# ASD2112.net
KiCad netlist of a schematic drawn in EAGLE
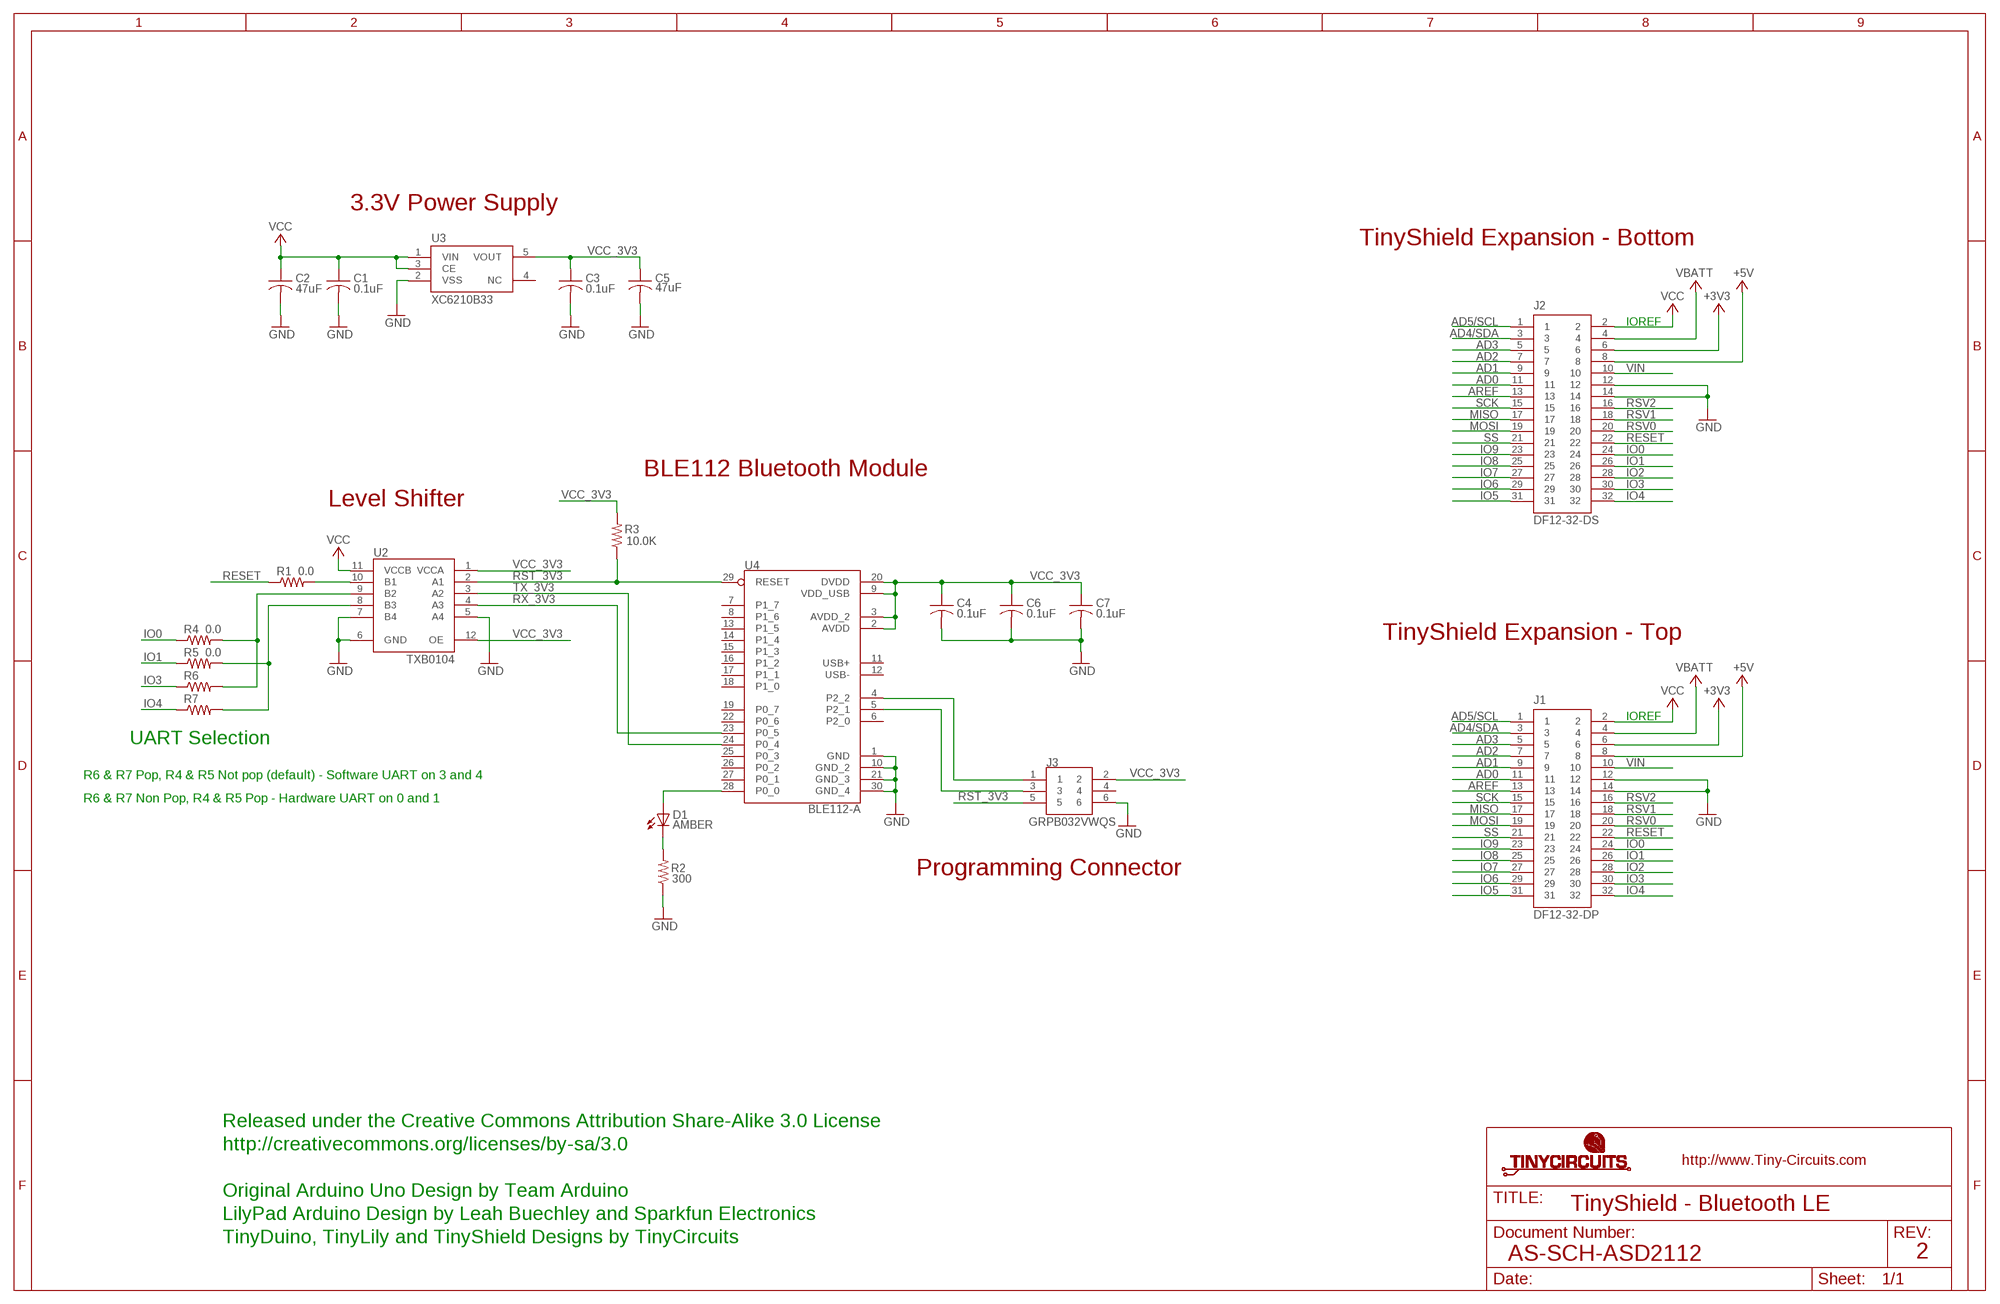
[diagram p0: schematic, sheet 1]

(export (version "E")
  (design (tool "Eeschema 10.0.6"))
  (components
    (comp (ref "C1")
      (value "0.1uF")
      (footprint "eagle-import:C0402")
      (fields (field (name "PARTNO") "AS-ITM-00008") (field (name "PARTNO_1") "AS-ITM-00008"))
      (libsource (lib "eagle-import") (part "AS-ITM-00008"))
    )
    (comp (ref "C2")
      (value "47uF")
      (footprint "eagle-import:C1206")
      (fields (field (name "PARTNUM") "AS-ITM-00049") (field (name "PARTNUM_1") "AS-ITM-00049"))
      (libsource (lib "eagle-import") (part "AS-ITM-00049"))
    )
    (comp (ref "C3")
      (value "0.1uF")
      (footprint "eagle-import:C0402")
      (fields (field (name "PARTNO") "AS-ITM-00008") (field (name "PARTNO_1") "AS-ITM-00008"))
      (libsource (lib "eagle-import") (part "AS-ITM-00008"))
    )
    (comp (ref "C4")
      (value "0.1uF")
      (footprint "eagle-import:C0402")
      (fields (field (name "PARTNO") "AS-ITM-00008") (field (name "PARTNO_1") "AS-ITM-00008"))
      (libsource (lib "eagle-import") (part "AS-ITM-00008"))
    )
    (comp (ref "C5")
      (value "47uF")
      (footprint "eagle-import:C1206")
      (fields (field (name "PARTNUM") "AS-ITM-00049"))
      (libsource (lib "eagle-import") (part "AS-ITM-00049"))
    )
    (comp (ref "C6")
      (value "0.1uF")
      (footprint "eagle-import:C0402")
      (fields (field (name "PARTNO") "AS-ITM-00008") (field (name "PARTNO_1") "AS-ITM-00008"))
      (libsource (lib "eagle-import") (part "AS-ITM-00008"))
    )
    (comp (ref "C7")
      (value "0.1uF")
      (footprint "eagle-import:C0402")
      (fields (field (name "PARTNO") "AS-ITM-00008") (field (name "PARTNO_1") "AS-ITM-00008"))
      (libsource (lib "eagle-import") (part "AS-ITM-00008"))
    )
    (comp (ref "D1")
      (value "AMBER")
      (footprint "eagle-import:LNJ_LED")
      (fields (field (name "PARTNO") "AS-ITM-00026"))
      (libsource (lib "eagle-import") (part "AS-ITM-00026"))
    )
    (comp (ref "J1")
      (value "DF12-32-DP")
      (footprint "eagle-import:DF12-32-DP")
      (fields (field (name "PARTNO") "AS-ITM-00015") (field (name "PARTNO_1") "AS-ITM-00015"))
      (libsource (lib "eagle-import") (part "AS-ITM-00015"))
    )
    (comp (ref "J2")
      (value "DF12-32-DS")
      (footprint "eagle-import:DF12-32-DS")
      (fields (field (name "PARTNO") "AS-ITM-00012") (field (name "PARTNO_1") "AS-ITM-00012"))
      (libsource (lib "eagle-import") (part "AS-ITM-00012"))
    )
    (comp (ref "J3")
      (value "GRPB032VWQS")
      (footprint "eagle-import:2X3_.05__SMT_HEADER")
      (fields (field (name "PARTNO") "AS-ITM-00034"))
      (libsource (lib "eagle-import") (part "AS-ITM-00034"))
    )
    (comp (ref "R1")
      (value "0.0")
      (footprint "eagle-import:0402")
      (fields (field (name "PARTNO") "AS-ITM-00076"))
      (libsource (lib "eagle-import") (part "AS-ITM-00076"))
    )
    (comp (ref "R2")
      (value "300")
      (footprint "eagle-import:0402")
      (fields (field (name "PARTNO") "AS-ITM-00016") (field (name "PARTNO_1") "AS-ITM-00016"))
      (libsource (lib "eagle-import") (part "AS-ITM-00016"))
    )
    (comp (ref "R3")
      (value "10.0K")
      (footprint "eagle-import:0402")
      (fields (field (name "PARTNO") "AS-ITM-00032"))
      (libsource (lib "eagle-import") (part "AS-ITM-00032"))
    )
    (comp (ref "R4")
      (value "0.0")
      (footprint "eagle-import:0402")
      (fields (field (name "PARTNO") "AS-ITM-00076") (field (name "PARTNO_1") "AS-ITM-00076"))
      (libsource (lib "eagle-import") (part "AS-ITM-00076"))
    )
    (comp (ref "R5")
      (value "0.0")
      (footprint "eagle-import:0402")
      (fields (field (name "PARTNO") "AS-ITM-00076") (field (name "PARTNO_1") "AS-ITM-00076"))
      (libsource (lib "eagle-import") (part "AS-ITM-00076"))
    )
    (comp (ref "R6")
      (value "0.0")
      (footprint "eagle-import:0402_SHORT")
      (libsource (lib "eagle-import") (part "AS-ITM-000760402_SHORT"))
    )
    (comp (ref "R7")
      (value "0.0")
      (footprint "eagle-import:0402_SHORT")
      (libsource (lib "eagle-import") (part "AS-ITM-000760402_SHORT"))
    )
    (comp (ref "U2")
      (value "TXB0104")
      (footprint "eagle-import:UQFN-12")
      (fields (field (name "PARTNO") "AS-ITM-00048"))
      (libsource (lib "eagle-import") (part "AS-ITM-00048"))
    )
    (comp (ref "U3")
      (value "XC6210B33")
      (footprint "eagle-import:SOT-25")
      (fields (field (name "PARTNO") "AS-ITM-00046"))
      (libsource (lib "eagle-import") (part "AS-ITM-00046"))
    )
    (comp (ref "U4")
      (value "BLE112-A")
      (footprint "eagle-import:BLUEGIGA_BLE_MODULE")
      (fields (field (name "PARTNO") "AS-ITM-00056"))
      (libsource (lib "eagle-import") (part "AS-ITM-00056"))
    )
  )
  (nets
    (net (code "1") (name "+3V3") (class "Default")
      (node (ref "J1") (pin "6") (pinfunction "6_6") (pintype "bidirectional"))
      (node (ref "J2") (pin "6") (pinfunction "6_6") (pintype "bidirectional"))
    )
    (net (code "2") (name "+5V") (class "Default")
      (node (ref "J1") (pin "8") (pinfunction "8_8") (pintype "bidirectional"))
      (node (ref "J2") (pin "8") (pinfunction "8_8") (pintype "bidirectional"))
    )
    (net (code "3") (name "/AD0") (class "Default")
      (node (ref "J1") (pin "11") (pinfunction "11_11") (pintype "bidirectional"))
      (node (ref "J2") (pin "11") (pinfunction "11_11") (pintype "bidirectional"))
    )
    (net (code "4") (name "/AD1") (class "Default")
      (node (ref "J1") (pin "9") (pinfunction "9_9") (pintype "bidirectional"))
      (node (ref "J2") (pin "9") (pinfunction "9_9") (pintype "bidirectional"))
    )
    (net (code "5") (name "/AD2") (class "Default")
      (node (ref "J1") (pin "7") (pinfunction "7_7") (pintype "bidirectional"))
      (node (ref "J2") (pin "7") (pinfunction "7_7") (pintype "bidirectional"))
    )
    (net (code "6") (name "/AD3") (class "Default")
      (node (ref "J1") (pin "5") (pinfunction "5_5") (pintype "bidirectional"))
      (node (ref "J2") (pin "5") (pinfunction "5_5") (pintype "bidirectional"))
    )
    (net (code "7") (name "/AD4{slash}SDA") (class "Default")
      (node (ref "J1") (pin "3") (pinfunction "3_3") (pintype "bidirectional"))
      (node (ref "J2") (pin "3") (pinfunction "3_3") (pintype "bidirectional"))
    )
    (net (code "8") (name "/AD5{slash}SCL") (class "Default")
      (node (ref "J1") (pin "1") (pinfunction "1_1") (pintype "bidirectional"))
      (node (ref "J2") (pin "1") (pinfunction "1_1") (pintype "bidirectional"))
    )
    (net (code "9") (name "/AREF") (class "Default")
      (node (ref "J1") (pin "13") (pinfunction "13_13") (pintype "bidirectional"))
      (node (ref "J2") (pin "13") (pinfunction "13_13") (pintype "bidirectional"))
    )
    (net (code "10") (name "/IO0") (class "Default")
      (node (ref "J1") (pin "24") (pinfunction "24_24") (pintype "bidirectional"))
      (node (ref "J2") (pin "24") (pinfunction "24_24") (pintype "bidirectional"))
      (node (ref "R4") (pin "1") (pinfunction "1_1") (pintype "passive"))
    )
    (net (code "11") (name "/IO1") (class "Default")
      (node (ref "J1") (pin "26") (pinfunction "26_26") (pintype "bidirectional"))
      (node (ref "J2") (pin "26") (pinfunction "26_26") (pintype "bidirectional"))
      (node (ref "R5") (pin "1") (pinfunction "1_1") (pintype "passive"))
    )
    (net (code "12") (name "/IO2") (class "Default")
      (node (ref "J1") (pin "28") (pinfunction "28_28") (pintype "bidirectional"))
      (node (ref "J2") (pin "28") (pinfunction "28_28") (pintype "bidirectional"))
    )
    (net (code "13") (name "/IO3") (class "Default")
      (node (ref "J1") (pin "30") (pinfunction "30_30") (pintype "bidirectional"))
      (node (ref "J2") (pin "30") (pinfunction "30_30") (pintype "bidirectional"))
      (node (ref "R6") (pin "1") (pinfunction "1_1") (pintype "passive"))
    )
    (net (code "14") (name "/IO4") (class "Default")
      (node (ref "J1") (pin "32") (pinfunction "32_32") (pintype "bidirectional"))
      (node (ref "J2") (pin "32") (pinfunction "32_32") (pintype "bidirectional"))
      (node (ref "R7") (pin "1") (pinfunction "1_1") (pintype "passive"))
    )
    (net (code "15") (name "/IO5") (class "Default")
      (node (ref "J1") (pin "31") (pinfunction "31_31") (pintype "bidirectional"))
      (node (ref "J2") (pin "31") (pinfunction "31_31") (pintype "bidirectional"))
    )
    (net (code "16") (name "/IO6") (class "Default")
      (node (ref "J1") (pin "29") (pinfunction "29_29") (pintype "bidirectional"))
      (node (ref "J2") (pin "29") (pinfunction "29_29") (pintype "bidirectional"))
    )
    (net (code "17") (name "/IO7") (class "Default")
      (node (ref "J1") (pin "27") (pinfunction "27_27") (pintype "bidirectional"))
      (node (ref "J2") (pin "27") (pinfunction "27_27") (pintype "bidirectional"))
    )
    (net (code "18") (name "/IO8") (class "Default")
      (node (ref "J1") (pin "25") (pinfunction "25_25") (pintype "bidirectional"))
      (node (ref "J2") (pin "25") (pinfunction "25_25") (pintype "bidirectional"))
    )
    (net (code "19") (name "/IO9") (class "Default")
      (node (ref "J1") (pin "23") (pinfunction "23_23") (pintype "bidirectional"))
      (node (ref "J2") (pin "23") (pinfunction "23_23") (pintype "bidirectional"))
    )
    (net (code "20") (name "/MISO") (class "Default")
      (node (ref "J1") (pin "17") (pinfunction "17_17") (pintype "bidirectional"))
      (node (ref "J2") (pin "17") (pinfunction "17_17") (pintype "bidirectional"))
    )
    (net (code "21") (name "/MOSI") (class "Default")
      (node (ref "J1") (pin "19") (pinfunction "19_19") (pintype "bidirectional"))
      (node (ref "J2") (pin "19") (pinfunction "19_19") (pintype "bidirectional"))
    )
    (net (code "22") (name "/RESET") (class "Default")
      (node (ref "J1") (pin "22") (pinfunction "22_22") (pintype "bidirectional"))
      (node (ref "J2") (pin "22") (pinfunction "22_22") (pintype "bidirectional"))
      (node (ref "R1") (pin "1") (pinfunction "1_1") (pintype "passive"))
    )
    (net (code "23") (name "/RST_3V3") (class "Default")
      (node (ref "J3") (pin "5") (pinfunction "5_5") (pintype "bidirectional"))
      (node (ref "R3") (pin "1") (pinfunction "1_1") (pintype "passive"))
      (node (ref "U2") (pin "2") (pinfunction "A1_2") (pintype "bidirectional"))
      (node (ref "U4") (pin "29") (pinfunction "RESET_29") (pintype "bidirectional"))
    )
    (net (code "24") (name "/RSV0") (class "Default")
      (node (ref "J1") (pin "20") (pinfunction "20_20") (pintype "bidirectional"))
      (node (ref "J2") (pin "20") (pinfunction "20_20") (pintype "bidirectional"))
    )
    (net (code "25") (name "/RSV1") (class "Default")
      (node (ref "J1") (pin "18") (pinfunction "18_18") (pintype "bidirectional"))
      (node (ref "J2") (pin "18") (pinfunction "18_18") (pintype "bidirectional"))
    )
    (net (code "26") (name "/RSV2") (class "Default")
      (node (ref "J1") (pin "16") (pinfunction "16_16") (pintype "bidirectional"))
      (node (ref "J2") (pin "16") (pinfunction "16_16") (pintype "bidirectional"))
    )
    (net (code "27") (name "/RX_3V3") (class "Default")
      (node (ref "U2") (pin "4") (pinfunction "A3_4") (pintype "bidirectional"))
      (node (ref "U4") (pin "23") (pinfunction "P0_5_23") (pintype "bidirectional"))
    )
    (net (code "28") (name "/SCK") (class "Default")
      (node (ref "J1") (pin "15") (pinfunction "15_15") (pintype "bidirectional"))
      (node (ref "J2") (pin "15") (pinfunction "15_15") (pintype "bidirectional"))
    )
    (net (code "29") (name "/SS") (class "Default")
      (node (ref "J1") (pin "21") (pinfunction "21_21") (pintype "bidirectional"))
      (node (ref "J2") (pin "21") (pinfunction "21_21") (pintype "bidirectional"))
    )
    (net (code "30") (name "/TX_3V3") (class "Default")
      (node (ref "U2") (pin "3") (pinfunction "A2_3") (pintype "bidirectional"))
      (node (ref "U4") (pin "24") (pinfunction "P0_4_24") (pintype "bidirectional"))
    )
    (net (code "31") (name "/VCC_3V3") (class "Default")
      (node (ref "C3") (pin "1") (pinfunction "1_1") (pintype "passive"))
      (node (ref "C4") (pin "1") (pinfunction "1_1") (pintype "passive"))
      (node (ref "C5") (pin "1") (pinfunction "1_1") (pintype "passive"))
      (node (ref "C6") (pin "1") (pinfunction "1_1") (pintype "passive"))
      (node (ref "C7") (pin "1") (pinfunction "1_1") (pintype "passive"))
      (node (ref "J3") (pin "2") (pinfunction "2_2") (pintype "bidirectional"))
      (node (ref "R3") (pin "2") (pinfunction "2_2") (pintype "passive"))
      (node (ref "U2") (pin "1") (pinfunction "VCCA_1") (pintype "bidirectional"))
      (node (ref "U2") (pin "12") (pinfunction "OE_12") (pintype "bidirectional"))
      (node (ref "U3") (pin "5") (pinfunction "VOUT_5") (pintype "bidirectional"))
      (node (ref "U4") (pin "2") (pinfunction "AVDD_2") (pintype "bidirectional"))
      (node (ref "U4") (pin "20") (pinfunction "DVDD_20") (pintype "bidirectional"))
      (node (ref "U4") (pin "3") (pinfunction "AVDD_2_3") (pintype "bidirectional"))
      (node (ref "U4") (pin "9") (pinfunction "VDD_USB_9") (pintype "bidirectional"))
    )
    (net (code "32") (name "/VIN") (class "Default")
      (node (ref "J1") (pin "10") (pinfunction "10_10") (pintype "bidirectional"))
      (node (ref "J2") (pin "10") (pinfunction "10_10") (pintype "bidirectional"))
    )
    (net (code "33") (name "GND") (class "Default")
      (node (ref "C1") (pin "2") (pinfunction "2_2") (pintype "passive"))
      (node (ref "C2") (pin "2") (pinfunction "2_2") (pintype "passive"))
      (node (ref "C3") (pin "2") (pinfunction "2_2") (pintype "passive"))
      (node (ref "C4") (pin "2") (pinfunction "2_2") (pintype "passive"))
      (node (ref "C5") (pin "2") (pinfunction "2_2") (pintype "passive"))
      (node (ref "C6") (pin "2") (pinfunction "2_2") (pintype "passive"))
      (node (ref "C7") (pin "2") (pinfunction "2_2") (pintype "passive"))
      (node (ref "J1") (pin "12") (pinfunction "12_12") (pintype "bidirectional"))
      (node (ref "J1") (pin "14") (pinfunction "14_14") (pintype "bidirectional"))
      (node (ref "J2") (pin "12") (pinfunction "12_12") (pintype "bidirectional"))
      (node (ref "J2") (pin "14") (pinfunction "14_14") (pintype "bidirectional"))
      (node (ref "J3") (pin "6") (pinfunction "6_6") (pintype "bidirectional"))
      (node (ref "R2") (pin "1") (pinfunction "1_1") (pintype "passive"))
      (node (ref "U2") (pin "5") (pinfunction "A4_5") (pintype "bidirectional"))
      (node (ref "U2") (pin "6") (pinfunction "GND_6") (pintype "bidirectional"))
      (node (ref "U2") (pin "7") (pinfunction "B4_7") (pintype "bidirectional"))
      (node (ref "U3") (pin "2") (pinfunction "VSS_2") (pintype "power_in"))
      (node (ref "U4") (pin "1") (pinfunction "GND_1") (pintype "bidirectional"))
      (node (ref "U4") (pin "10") (pinfunction "GND_2_10") (pintype "bidirectional"))
      (node (ref "U4") (pin "21") (pinfunction "GND_3_21") (pintype "bidirectional"))
      (node (ref "U4") (pin "30") (pinfunction "GND_4_30") (pintype "bidirectional"))
    )
    (net (code "34") (name "Net-(D1-PadC)") (class "Default")
      (node (ref "D1") (pin "C") (pinfunction "C_C") (pintype "passive"))
      (node (ref "R2") (pin "2") (pinfunction "2_2") (pintype "passive"))
    )
    (net (code "35") (name "Net-(U2-B1)") (class "Default")
      (node (ref "R1") (pin "2") (pinfunction "2_2") (pintype "passive"))
      (node (ref "U2") (pin "10") (pinfunction "B1_10") (pintype "bidirectional"))
    )
    (net (code "36") (name "Net-(U2-B2)") (class "Default")
      (node (ref "R4") (pin "2") (pinfunction "2_2") (pintype "passive"))
      (node (ref "R6") (pin "2") (pinfunction "2_2") (pintype "passive"))
      (node (ref "U2") (pin "9") (pinfunction "B2_9") (pintype "bidirectional"))
    )
    (net (code "37") (name "Net-(U2-B3)") (class "Default")
      (node (ref "R5") (pin "2") (pinfunction "2_2") (pintype "passive"))
      (node (ref "R7") (pin "2") (pinfunction "2_2") (pintype "passive"))
      (node (ref "U2") (pin "8") (pinfunction "B3_8") (pintype "bidirectional"))
    )
    (net (code "38") (name "Net-(U4-P0_0)") (class "Default")
      (node (ref "D1") (pin "A") (pinfunction "A_A") (pintype "passive"))
      (node (ref "U4") (pin "28") (pinfunction "P0_0_28") (pintype "bidirectional"))
    )
    (net (code "39") (name "Net-(U4-P2_1)") (class "Default")
      (node (ref "J3") (pin "3") (pinfunction "3_3") (pintype "bidirectional"))
      (node (ref "U4") (pin "5") (pinfunction "P2_1_5") (pintype "bidirectional"))
    )
    (net (code "40") (name "Net-(U4-P2_2)") (class "Default")
      (node (ref "J3") (pin "1") (pinfunction "1_1") (pintype "bidirectional"))
      (node (ref "U4") (pin "4") (pinfunction "P2_2_4") (pintype "bidirectional"))
    )
    (net (code "41") (name "VBATT") (class "Default")
      (node (ref "J1") (pin "4") (pinfunction "4_4") (pintype "bidirectional"))
      (node (ref "J2") (pin "4") (pinfunction "4_4") (pintype "bidirectional"))
    )
    (net (code "42") (name "VCC") (class "Default")
      (node (ref "C1") (pin "1") (pinfunction "1_1") (pintype "passive"))
      (node (ref "C2") (pin "1") (pinfunction "1_1") (pintype "passive"))
      (node (ref "J1") (pin "2") (pinfunction "2_2") (pintype "bidirectional"))
      (node (ref "J2") (pin "2") (pinfunction "2_2") (pintype "bidirectional"))
      (node (ref "U2") (pin "11") (pinfunction "VCCB_11") (pintype "bidirectional"))
      (node (ref "U3") (pin "1") (pinfunction "VIN_1") (pintype "bidirectional"))
      (node (ref "U3") (pin "3") (pinfunction "CE_3") (pintype "bidirectional"))
    )
    (net (code "43") (name "unconnected-(J3-Pad4)") (class "Default")
      (node (ref "J3") (pin "4") (pinfunction "4_4") (pintype "bidirectional"))
    )
    (net (code "44") (name "unconnected-(U3-NC-Pad4)") (class "Default")
      (node (ref "U3") (pin "4") (pinfunction "NC_4") (pintype "bidirectional"))
    )
    (net (code "45") (name "unconnected-(U4-P0_1-Pad27)") (class "Default")
      (node (ref "U4") (pin "27") (pinfunction "P0_1_27") (pintype "bidirectional"))
    )
    (net (code "46") (name "unconnected-(U4-P0_2-Pad26)") (class "Default")
      (node (ref "U4") (pin "26") (pinfunction "P0_2_26") (pintype "bidirectional"))
    )
    (net (code "47") (name "unconnected-(U4-P0_3-Pad25)") (class "Default")
      (node (ref "U4") (pin "25") (pinfunction "P0_3_25") (pintype "bidirectional"))
    )
    (net (code "48") (name "unconnected-(U4-P0_6-Pad22)") (class "Default")
      (node (ref "U4") (pin "22") (pinfunction "P0_6_22") (pintype "bidirectional"))
    )
    (net (code "49") (name "unconnected-(U4-P0_7-Pad19)") (class "Default")
      (node (ref "U4") (pin "19") (pinfunction "P0_7_19") (pintype "bidirectional"))
    )
    (net (code "50") (name "unconnected-(U4-P1_0-Pad18)") (class "Default")
      (node (ref "U4") (pin "18") (pinfunction "P1_0_18") (pintype "bidirectional"))
    )
    (net (code "51") (name "unconnected-(U4-P1_1-Pad17)") (class "Default")
      (node (ref "U4") (pin "17") (pinfunction "P1_1_17") (pintype "bidirectional"))
    )
    (net (code "52") (name "unconnected-(U4-P1_2-Pad16)") (class "Default")
      (node (ref "U4") (pin "16") (pinfunction "P1_2_16") (pintype "bidirectional"))
    )
    (net (code "53") (name "unconnected-(U4-P1_3-Pad15)") (class "Default")
      (node (ref "U4") (pin "15") (pinfunction "P1_3_15") (pintype "bidirectional"))
    )
    (net (code "54") (name "unconnected-(U4-P1_4-Pad14)") (class "Default")
      (node (ref "U4") (pin "14") (pinfunction "P1_4_14") (pintype "bidirectional"))
    )
    (net (code "55") (name "unconnected-(U4-P1_5-Pad13)") (class "Default")
      (node (ref "U4") (pin "13") (pinfunction "P1_5_13") (pintype "bidirectional"))
    )
    (net (code "56") (name "unconnected-(U4-P1_6-Pad8)") (class "Default")
      (node (ref "U4") (pin "8") (pinfunction "P1_6_8") (pintype "bidirectional"))
    )
    (net (code "57") (name "unconnected-(U4-P1_7-Pad7)") (class "Default")
      (node (ref "U4") (pin "7") (pinfunction "P1_7_7") (pintype "bidirectional"))
    )
    (net (code "58") (name "unconnected-(U4-P2_0-Pad6)") (class "Default")
      (node (ref "U4") (pin "6") (pinfunction "P2_0_6") (pintype "bidirectional"))
    )
    (net (code "59") (name "unconnected-(U4-USB+-Pad11)") (class "Default")
      (node (ref "U4") (pin "11") (pinfunction "USB+_11") (pintype "bidirectional"))
    )
    (net (code "60") (name "unconnected-(U4-USB--Pad12)") (class "Default")
      (node (ref "U4") (pin "12") (pinfunction "USB-_12") (pintype "bidirectional"))
    )
  )
)
